# XBee.net
KiCad netlist of a schematic drawn in Altium Designer
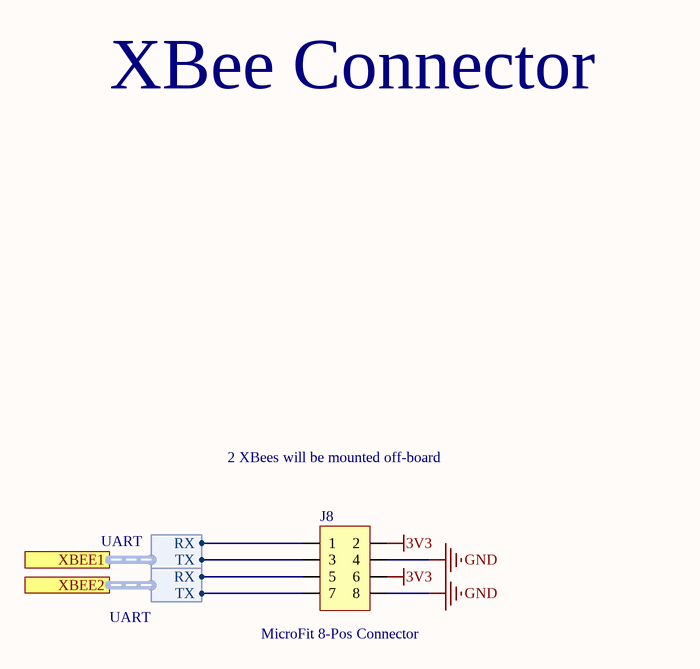
[diagram p0: XBee.SchDoc]

(export (version "E")
  (design (tool "Eeschema 10.0.6"))
  (components
    (comp (ref "J8")
      (value "MicroFit 8-Pos Connector")
      (footprint "Microfit-8Pos")
      (description "Molex MicroFit 8-Pos Connector")
      (libsource (lib "LaunchyRIOComponents") (part "Micro-Fit 8Pos"))
    )
  )
  (nets
    (net (code "5") (name "3V3") (class "Default")
      (node (ref "J8") (pin "2") (pinfunction "2_2") (pintype "passive"))
      (node (ref "J8") (pin "6") (pinfunction "6_6") (pintype "passive"))
    )
    (net (code "6") (name "GND") (class "Default")
      (node (ref "J8") (pin "4") (pinfunction "4_4") (pintype "passive"))
      (node (ref "J8") (pin "8") (pinfunction "8_8") (pintype "passive"))
    )
    (net (code "7") (name "unconnected-(J8-Pad1)") (class "Default")
      (node (ref "J8") (pin "1") (pinfunction "1_1") (pintype "passive"))
    )
    (net (code "8") (name "unconnected-(J8-Pad3)") (class "Default")
      (node (ref "J8") (pin "3") (pinfunction "3_3") (pintype "passive"))
    )
    (net (code "9") (name "unconnected-(J8-Pad5)") (class "Default")
      (node (ref "J8") (pin "5") (pinfunction "5_5") (pintype "passive"))
    )
    (net (code "10") (name "unconnected-(J8-Pad7)") (class "Default")
      (node (ref "J8") (pin "7") (pinfunction "7_7") (pintype "passive"))
    )
  )
)
